# sensor-board.net
KiCad netlist of a schematic drawn in EAGLE
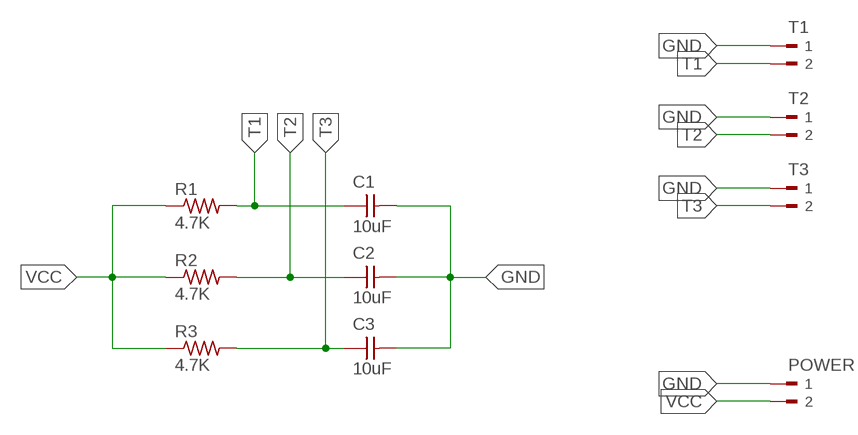
[diagram p0: schematic, sheet 1]

(export (version "E")
  (design (tool "Eeschema 10.0.6"))
  (components
    (comp (ref "C1")
      (value "10uF")
      (footprint "eagle-import:1206")
      (libsource (lib "eagle-import") (part "UNPOLARIZED_CAPACITOR1206"))
    )
    (comp (ref "C2")
      (value "10uF")
      (footprint "eagle-import:1206")
      (libsource (lib "eagle-import") (part "UNPOLARIZED_CAPACITOR1206"))
    )
    (comp (ref "C3")
      (value "10uF")
      (footprint "eagle-import:1206")
      (libsource (lib "eagle-import") (part "UNPOLARIZED_CAPACITOR1206"))
    )
    (comp (ref "POWER")
      (value "PM5.08/2/90BLK")
      (footprint "eagle-import:WEIDMULLER_PM5.08_2")
      (fields (field (name "MPN") "PM5.08/2/90 BLK"))
      (libsource (lib "eagle-import") (part "PM5.08/2/90BLK"))
    )
    (comp (ref "R1")
      (value "4.7K")
      (footprint "eagle-import:R1206FAB")
      (libsource (lib "eagle-import") (part "RES-US1206FAB"))
    )
    (comp (ref "R2")
      (value "4.7K")
      (footprint "eagle-import:R1206FAB")
      (libsource (lib "eagle-import") (part "RES-US1206FAB"))
    )
    (comp (ref "R3")
      (value "4.7K")
      (footprint "eagle-import:R1206FAB")
      (libsource (lib "eagle-import") (part "RES-US1206FAB"))
    )
    (comp (ref "T1")
      (value "PM5.08/2/90BLK")
      (footprint "eagle-import:WEIDMULLER_PM5.08_2")
      (fields (field (name "MPN") "PM5.08/2/90 BLK"))
      (libsource (lib "eagle-import") (part "PM5.08/2/90BLK"))
    )
    (comp (ref "T2")
      (value "PM5.08/2/90BLK")
      (footprint "eagle-import:WEIDMULLER_PM5.08_2")
      (fields (field (name "MPN") "PM5.08/2/90 BLK"))
      (libsource (lib "eagle-import") (part "PM5.08/2/90BLK"))
    )
    (comp (ref "T3")
      (value "PM5.08/2/90BLK")
      (footprint "eagle-import:WEIDMULLER_PM5.08_2")
      (fields (field (name "MPN") "PM5.08/2/90 BLK"))
      (libsource (lib "eagle-import") (part "PM5.08/2/90BLK"))
    )
  )
  (nets
    (net (code "1") (name "GND") (class "Default")
      (node (ref "C1") (pin "2") (pinfunction "2_2") (pintype "passive"))
      (node (ref "C2") (pin "2") (pinfunction "2_2") (pintype "passive"))
      (node (ref "C3") (pin "2") (pinfunction "2_2") (pintype "passive"))
      (node (ref "POWER") (pin "1") (pinfunction "1_1") (pintype "passive"))
      (node (ref "T1") (pin "1") (pinfunction "1_1") (pintype "passive"))
      (node (ref "T2") (pin "1") (pinfunction "1_1") (pintype "passive"))
      (node (ref "T3") (pin "1") (pinfunction "1_1") (pintype "passive"))
    )
    (net (code "2") (name "T1") (class "Default")
      (node (ref "C1") (pin "1") (pinfunction "1_1") (pintype "passive"))
      (node (ref "R1") (pin "2") (pinfunction "2_2") (pintype "passive"))
      (node (ref "T1") (pin "2") (pinfunction "2_2") (pintype "passive"))
    )
    (net (code "3") (name "T2") (class "Default")
      (node (ref "C2") (pin "1") (pinfunction "1_1") (pintype "passive"))
      (node (ref "R2") (pin "2") (pinfunction "2_2") (pintype "passive"))
      (node (ref "T2") (pin "2") (pinfunction "2_2") (pintype "passive"))
    )
    (net (code "4") (name "T3") (class "Default")
      (node (ref "C3") (pin "1") (pinfunction "1_1") (pintype "passive"))
      (node (ref "R3") (pin "2") (pinfunction "2_2") (pintype "passive"))
      (node (ref "T3") (pin "2") (pinfunction "2_2") (pintype "passive"))
    )
    (net (code "5") (name "VCC") (class "Default")
      (node (ref "POWER") (pin "2") (pinfunction "2_2") (pintype "passive"))
      (node (ref "R1") (pin "1") (pinfunction "1_1") (pintype "passive"))
      (node (ref "R2") (pin "1") (pinfunction "1_1") (pintype "passive"))
      (node (ref "R3") (pin "1") (pinfunction "1_1") (pintype "passive"))
    )
  )
)
